# tps63020-buck-boost-flashlight-driver-17.net
KiCad netlist of a schematic drawn in EAGLE
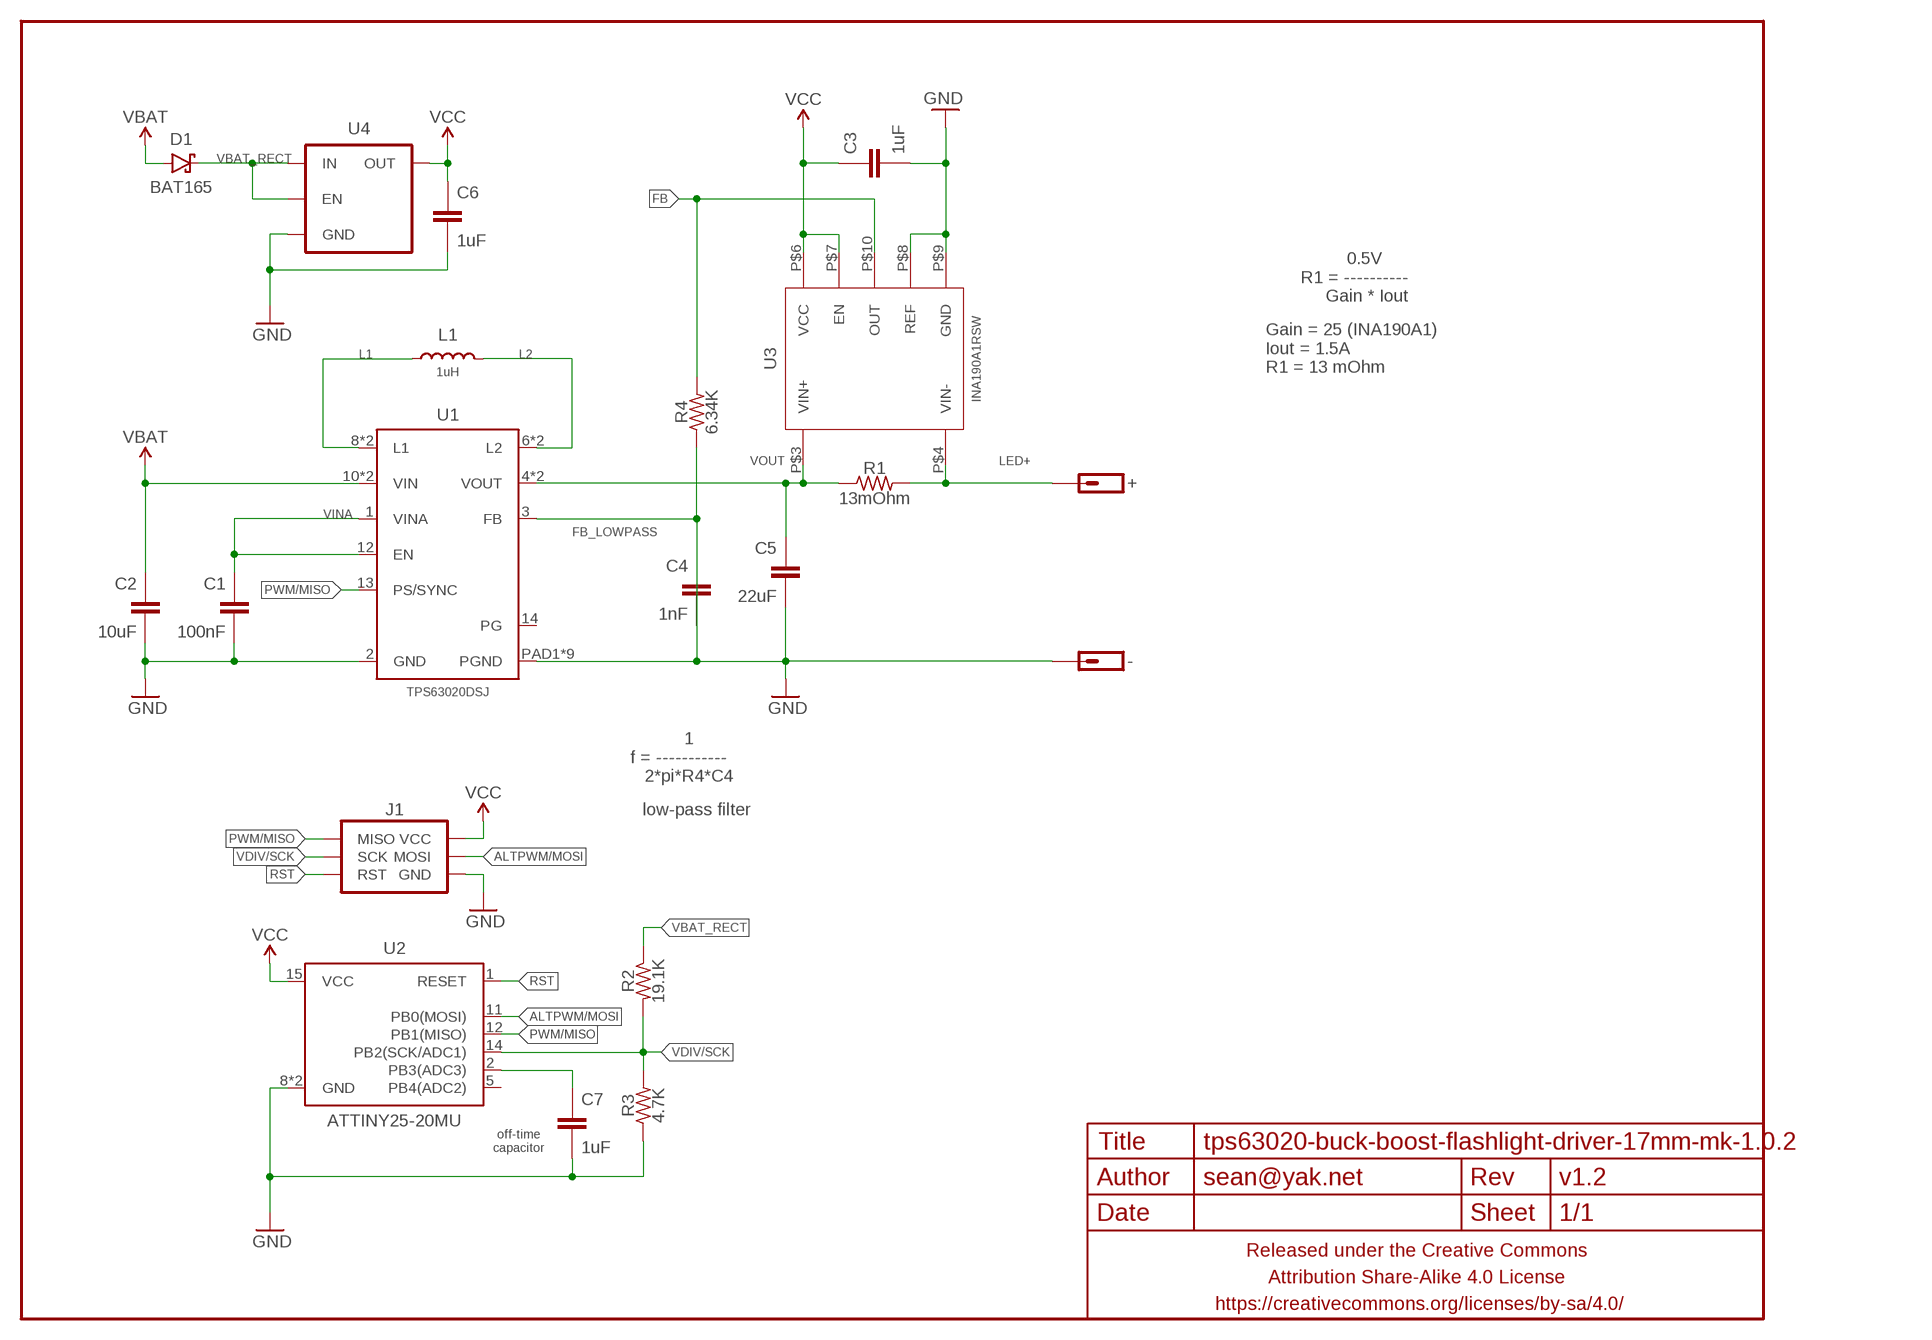
[diagram p0: schematic, sheet 1]

(export (version "E")
  (design (tool "Eeschema 10.0.6"))
  (components
    (comp (ref "+")
      (value "M01PTH-1MM-CIR-NS")
      (footprint "eagle-import:1X01-1MM-CIR-NS")
      (libsource (lib "eagle-import") (part "M01PTH-1MM-CIR-NS"))
    )
    (comp (ref "-")
      (value "M01PTH-1MM-CIR-NS")
      (footprint "eagle-import:1X01-1MM-CIR-NS")
      (libsource (lib "eagle-import") (part "M01PTH-1MM-CIR-NS"))
    )
    (comp (ref "C1")
      (value "100nF")
      (footprint "eagle-import:C0402")
      (libsource (lib "eagle-import") (part "CAPACITOR-CERAMICC0402"))
    )
    (comp (ref "C2")
      (value "10uF")
      (footprint "eagle-import:C0805-TIGHTER")
      (libsource (lib "eagle-import") (part "CAPACITOR-CERAMICC0805-TIGHTER"))
    )
    (comp (ref "C3")
      (value "1uF")
      (footprint "eagle-import:C0402")
      (libsource (lib "eagle-import") (part "CAPACITOR-CERAMICC0402"))
    )
    (comp (ref "C4")
      (value "1nF")
      (footprint "eagle-import:C0402")
      (libsource (lib "eagle-import") (part "CAPACITOR-CERAMICC0402"))
    )
    (comp (ref "C5")
      (value "22uF")
      (footprint "eagle-import:C0805-TIGHTER")
      (libsource (lib "eagle-import") (part "CAPACITOR-CERAMICC0805-TIGHTER"))
    )
    (comp (ref "C6")
      (value "1uF")
      (footprint "eagle-import:C0402")
      (libsource (lib "eagle-import") (part "CAPACITOR-CERAMICC0402"))
    )
    (comp (ref "C7")
      (value "1uF")
      (footprint "eagle-import:C0402")
      (libsource (lib "eagle-import") (part "CAPACITOR-CERAMICC0402"))
    )
    (comp (ref "D1")
      (value "BAT165")
      (footprint "eagle-import:SOD323-SCHOTTKY")
      (libsource (lib "eagle-import") (part "DIODE-SCHOTTKYSOD323"))
    )
    (comp (ref "FRAME1")
      (value "FRAME-LETTERNO_PACKAGE")
      (footprint "eagle-import:DUMMY")
      (fields
        (field (name "DESIGNER") "sean@yak.net")
        (field (name "VERSION") "v1.2")
        (field (name "DESIGNER_1") "sean@yak.net")
        (field (name "VERSION_1") "v1.2")
      )
      (libsource (lib "eagle-import") (part "FRAME-LETTERNO_PACKAGE"))
    )
    (comp (ref "J1")
      (value "AVR_SPI_PRG_6SMD-1.27MM")
      (footprint "eagle-import:2X3-1.27MM-SMD")
      (libsource (lib "eagle-import") (part "AVR_SPI_PRG_6SMD-1.27MM"))
    )
    (comp (ref "L1")
      (value "1uH")
      (footprint "eagle-import:XAL50X0")
      (libsource (lib "eagle-import") (part "INDUCTORXAL50X0"))
    )
    (comp (ref "R1")
      (value "13mOhm")
      (footprint "eagle-import:R0805-TIGHTER")
      (libsource (lib "eagle-import") (part "RESISTORR0805-TIGHTER"))
    )
    (comp (ref "R2")
      (value "19.1K")
      (footprint "eagle-import:R0402")
      (libsource (lib "eagle-import") (part "RESISTORR0402"))
    )
    (comp (ref "R3")
      (value "4.7K")
      (footprint "eagle-import:R0402")
      (libsource (lib "eagle-import") (part "RESISTORR0402"))
    )
    (comp (ref "R4")
      (value "6.34K")
      (footprint "eagle-import:R0402")
      (libsource (lib "eagle-import") (part "RESISTORR0402"))
    )
    (comp (ref "U1")
      (value "TPS63020DSJ")
      (footprint "eagle-import:VSON-14-4MMX3MM")
      (libsource (lib "eagle-import") (part "TPS63020DSJ"))
    )
    (comp (ref "U2")
      (value "ATTINY25-20MU")
      (footprint "eagle-import:QFN20")
      (libsource (lib "eagle-import") (part "ATTINY45TINY85-20-QFN"))
    )
    (comp (ref "U3")
      (value "INA190A1RSW")
      (footprint "eagle-import:UQFN-10")
      (libsource (lib "eagle-import") (part "INA190RSW"))
    )
    (comp (ref "U4")
      (value "V_REG_ENTLV700")
      (footprint "eagle-import:SC70")
      (libsource (lib "eagle-import") (part "V_REG_ENTLV700"))
    )
  )
  (nets
    (net (code "1") (name "/FB_LOWPASS") (class "Default")
      (node (ref "C4") (pin "2") (pinfunction "2_2") (pintype "passive"))
      (node (ref "R4") (pin "1") (pinfunction "1_1") (pintype "passive"))
      (node (ref "U1") (pin "3") (pinfunction "FB_3") (pintype "bidirectional"))
    )
    (net (code "2") (name "/L1") (class "Default")
      (node (ref "L1") (pin "P$1") (pinfunction "1_P$1") (pintype "passive"))
      (node (ref "U1") (pin "8") (pinfunction "L1_8") (pintype "bidirectional"))
      (node (ref "U1") (pin "9") (pinfunction "L1_9") (pintype "bidirectional"))
    )
    (net (code "3") (name "/L2") (class "Default")
      (node (ref "L1") (pin "P$2") (pinfunction "2_P$2") (pintype "passive"))
      (node (ref "U1") (pin "6") (pinfunction "L2_6") (pintype "bidirectional"))
      (node (ref "U1") (pin "7") (pinfunction "L2_7") (pintype "bidirectional"))
    )
    (net (code "4") (name "/LED+") (class "Default")
      (node (ref "+") (pin "1") (pinfunction "1_1") (pintype "passive"))
      (node (ref "R1") (pin "2") (pinfunction "2_2") (pintype "passive"))
      (node (ref "U3") (pin "P$4") (pinfunction "VIN-_P$4") (pintype "bidirectional"))
    )
    (net (code "5") (name "/VINA") (class "Default")
      (node (ref "C1") (pin "1") (pinfunction "1_1") (pintype "passive"))
      (node (ref "U1") (pin "1") (pinfunction "VINA_1") (pintype "bidirectional"))
      (node (ref "U1") (pin "12") (pinfunction "EN_12") (pintype "bidirectional"))
    )
    (net (code "6") (name "/VOUT") (class "Default")
      (node (ref "C5") (pin "1") (pinfunction "1_1") (pintype "passive"))
      (node (ref "R1") (pin "1") (pinfunction "1_1") (pintype "passive"))
      (node (ref "U1") (pin "4") (pinfunction "VOUT_4") (pintype "bidirectional"))
      (node (ref "U1") (pin "5") (pinfunction "VOUT_5") (pintype "bidirectional"))
      (node (ref "U3") (pin "P$3") (pinfunction "VIN+_P$3") (pintype "bidirectional"))
    )
    (net (code "7") (name "ALTPWM{slash}MOSI") (class "Default")
      (node (ref "J1") (pin "4") (pinfunction "MOSI_4") (pintype "passive"))
      (node (ref "U2") (pin "11") (pinfunction "PB0(MOSI)_11") (pintype "bidirectional"))
    )
    (net (code "8") (name "FB") (class "Default")
      (node (ref "R4") (pin "2") (pinfunction "2_2") (pintype "passive"))
      (node (ref "U3") (pin "P$10") (pinfunction "OUT_P$10") (pintype "bidirectional"))
    )
    (net (code "9") (name "GND") (class "Default")
      (node (ref "-") (pin "1") (pinfunction "1_1") (pintype "passive"))
      (node (ref "C1") (pin "2") (pinfunction "2_2") (pintype "passive"))
      (node (ref "C2") (pin "2") (pinfunction "2_2") (pintype "passive"))
      (node (ref "C3") (pin "2") (pinfunction "2_2") (pintype "passive"))
      (node (ref "C4") (pin "1") (pinfunction "1_1") (pintype "passive"))
      (node (ref "C5") (pin "2") (pinfunction "2_2") (pintype "passive"))
      (node (ref "C6") (pin "2") (pinfunction "2_2") (pintype "passive"))
      (node (ref "C7") (pin "2") (pinfunction "2_2") (pintype "passive"))
      (node (ref "J1") (pin "6") (pinfunction "GND_6") (pintype "passive"))
      (node (ref "R3") (pin "1") (pinfunction "1_1") (pintype "passive"))
      (node (ref "U1") (pin "2") (pinfunction "GND_2") (pintype "bidirectional"))
      (node (ref "U1") (pin "PAD1") (pinfunction "PGND_PAD1") (pintype "bidirectional"))
      (node (ref "U1") (pin "PAD2") (pinfunction "PGND_PAD2") (pintype "bidirectional"))
      (node (ref "U1") (pin "PAD3") (pinfunction "PGND_PAD3") (pintype "bidirectional"))
      (node (ref "U1") (pin "PAD4") (pinfunction "PGND_PAD4") (pintype "bidirectional"))
      (node (ref "U1") (pin "PAD5") (pinfunction "PGND_PAD5") (pintype "bidirectional"))
      (node (ref "U1") (pin "PAD6") (pinfunction "PGND_PAD6") (pintype "bidirectional"))
      (node (ref "U1") (pin "PAD7") (pinfunction "PGND_PAD7") (pintype "bidirectional"))
      (node (ref "U1") (pin "PAD8") (pinfunction "PGND_PAD8") (pintype "bidirectional"))
      (node (ref "U1") (pin "PADCENTER") (pinfunction "PGND_PADCENTER") (pintype "bidirectional"))
      (node (ref "U2") (pin "8") (pinfunction "GND_8") (pintype "bidirectional"))
      (node (ref "U2") (pin "PAD") (pinfunction "GND_PAD") (pintype "bidirectional"))
      (node (ref "U3") (pin "P$8") (pinfunction "REF_P$8") (pintype "bidirectional"))
      (node (ref "U3") (pin "P$9") (pinfunction "GND_P$9") (pintype "bidirectional"))
      (node (ref "U4") (pin "2") (pinfunction "GND_2") (pintype "input"))
    )
    (net (code "10") (name "Net-(U2-PB3(ADC3))") (class "Default")
      (node (ref "C7") (pin "1") (pinfunction "1_1") (pintype "passive"))
      (node (ref "U2") (pin "2") (pinfunction "PB3(ADC3)_2") (pintype "bidirectional"))
    )
    (net (code "11") (name "PWM{slash}MISO") (class "Default")
      (node (ref "J1") (pin "1") (pinfunction "MISO_1") (pintype "passive"))
      (node (ref "U1") (pin "13") (pinfunction "PS/SYNC_13") (pintype "bidirectional"))
      (node (ref "U2") (pin "12") (pinfunction "PB1(MISO)_12") (pintype "bidirectional"))
    )
    (net (code "12") (name "RST") (class "Default")
      (node (ref "J1") (pin "5") (pinfunction "RST_5") (pintype "passive"))
      (node (ref "U2") (pin "1") (pinfunction "RESET_1") (pintype "bidirectional"))
    )
    (net (code "13") (name "VBAT") (class "Default")
      (node (ref "C2") (pin "1") (pinfunction "1_1") (pintype "passive"))
      (node (ref "D1") (pin "A") (pinfunction "A_A") (pintype "passive"))
      (node (ref "U1") (pin "10") (pinfunction "VIN_10") (pintype "bidirectional"))
      (node (ref "U1") (pin "11") (pinfunction "VIN_11") (pintype "bidirectional"))
    )
    (net (code "14") (name "VBAT_RECT") (class "Default")
      (node (ref "D1") (pin "C") (pinfunction "C_C") (pintype "passive"))
      (node (ref "R2") (pin "1") (pinfunction "1_1") (pintype "passive"))
      (node (ref "U4") (pin "1") (pinfunction "IN_1") (pintype "input"))
      (node (ref "U4") (pin "3") (pinfunction "EN_3") (pintype "input"))
    )
    (net (code "15") (name "VCC") (class "Default")
      (node (ref "C3") (pin "1") (pinfunction "1_1") (pintype "passive"))
      (node (ref "C6") (pin "1") (pinfunction "1_1") (pintype "passive"))
      (node (ref "J1") (pin "2") (pinfunction "VCC_2") (pintype "passive"))
      (node (ref "U2") (pin "15") (pinfunction "VCC_15") (pintype "bidirectional"))
      (node (ref "U3") (pin "P$6") (pinfunction "VCC_P$6") (pintype "bidirectional"))
      (node (ref "U3") (pin "P$7") (pinfunction "EN_P$7") (pintype "bidirectional"))
      (node (ref "U4") (pin "5") (pinfunction "OUT_5") (pintype "passive"))
    )
    (net (code "16") (name "VDIV{slash}SCK") (class "Default")
      (node (ref "J1") (pin "3") (pinfunction "SCK_3") (pintype "passive"))
      (node (ref "R2") (pin "2") (pinfunction "2_2") (pintype "passive"))
      (node (ref "R3") (pin "2") (pinfunction "2_2") (pintype "passive"))
      (node (ref "U2") (pin "14") (pinfunction "PB2(SCK/ADC1)_14") (pintype "bidirectional"))
    )
    (net (code "17") (name "unconnected-(U1-PG-Pad14)") (class "Default")
      (node (ref "U1") (pin "14") (pinfunction "PG_14") (pintype "bidirectional"))
    )
    (net (code "18") (name "unconnected-(U2-PB4(ADC2)-Pad5)") (class "Default")
      (node (ref "U2") (pin "5") (pinfunction "PB4(ADC2)_5") (pintype "bidirectional"))
    )
  )
)
